# PositivePwr.net
KiCad netlist of a schematic drawn in Altium Designer
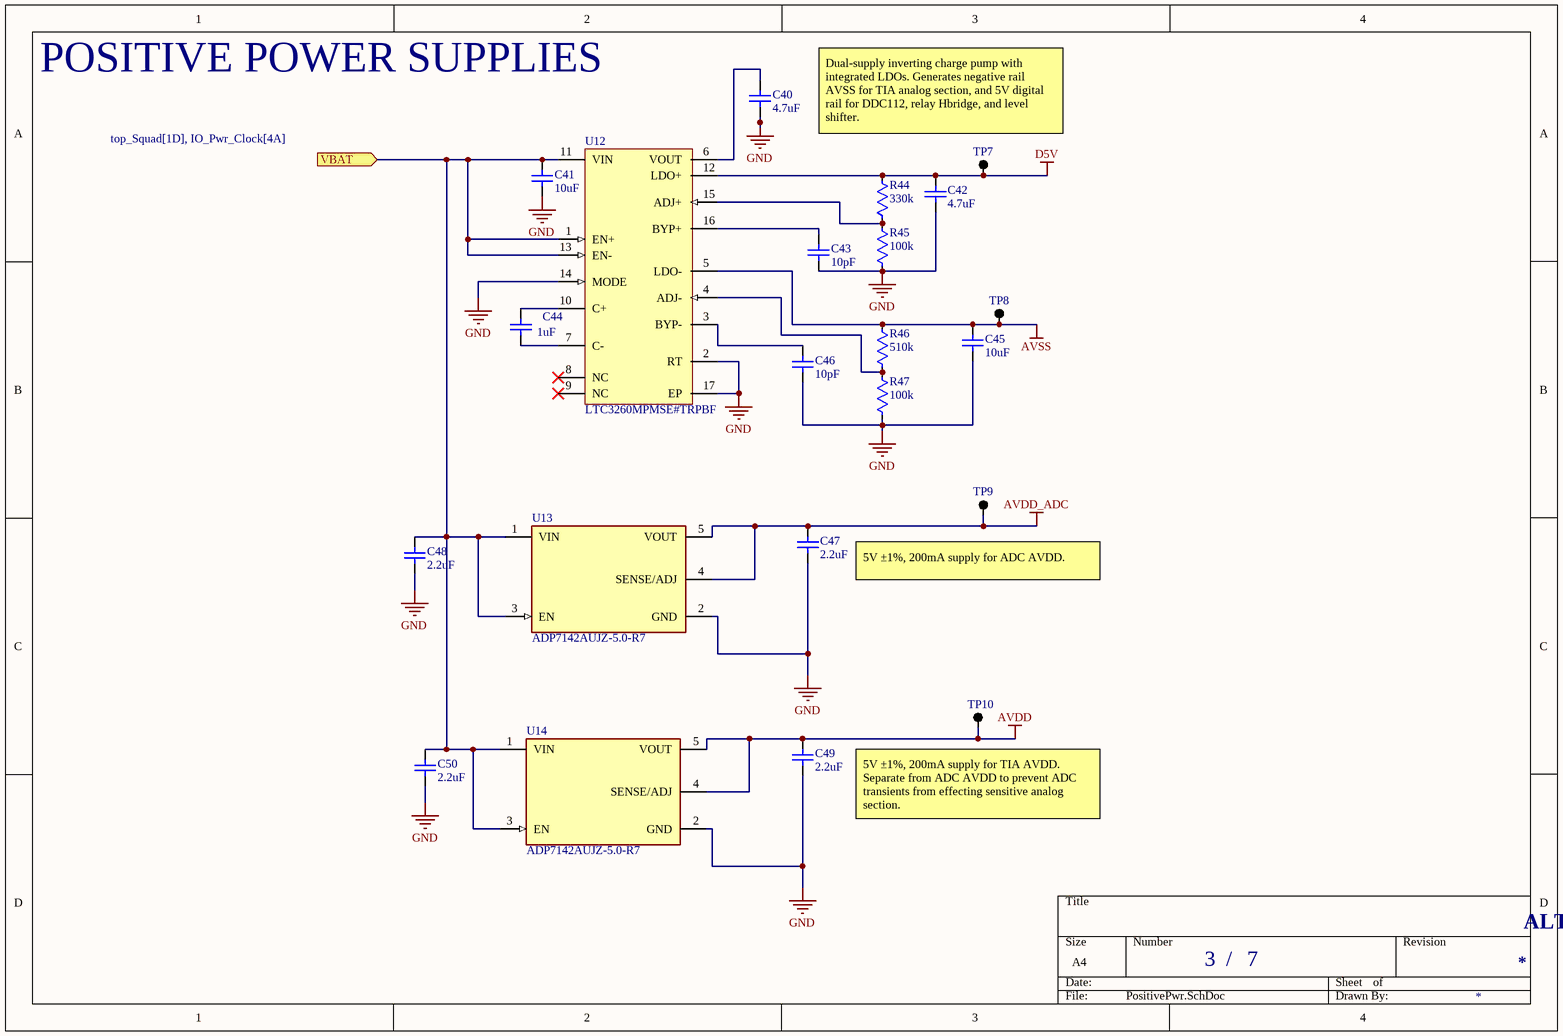
[diagram p0: PositivePwr.SchDoc]

(export (version "E")
  (design (tool "Eeschema 10.0.6"))
  (components
    (comp (ref "C40")
      (value "4.7uF")
      (footprint "CAP 0805 IPC MID DENSITY")
      (description "Murata GRM21BR61E106KA73L - Cap Ceramic 10uF 10% 25V X5R 0805")
      (fields (field (name "MF") "Murata") (field (name "MP") "GRM21BR61E106KA73L"))
      (libsource (lib "ALTAIR_PD_Capacitors") (part "CAP"))
    )
    (comp (ref "C41")
      (value "10uF")
      (footprint "CAP 0805 IPC MID DENSITY")
      (description "Murata GRM21BR61E106KA73L - Cap Ceramic 10uF 10% 25V X5R 0805")
      (fields (field (name "MF") "Murata") (field (name "MP") "GRM21BR61E106KA73L"))
      (libsource (lib "ALTAIR_PD_Capacitors") (part "CAP"))
    )
    (comp (ref "C42")
      (value "4.7uF")
      (footprint "CAP 0805 IPC MID DENSITY")
      (description "Murata GRM21BR61E106KA73L - Cap Ceramic 10uF 10% 25V X5R 0805")
      (fields (field (name "MF") "Murata") (field (name "MP") "GRM21BR61E106KA73L"))
      (libsource (lib "ALTAIR_PD_Capacitors") (part "CAP"))
    )
    (comp (ref "C43")
      (value "10pF")
      (footprint "CAP 0603 IPC MID DENSITY MURATA")
      (description "Murata GRM21BR61E106KA73L - Cap Ceramic 10uF 10% 25V X5R 0805")
      (fields (field (name "MF") "Murata") (field (name "MP") "GRM21BR61E106KA73L"))
      (libsource (lib "ALTAIR_PD_Capacitors") (part "CAP"))
    )
    (comp (ref "C44")
      (value "1uF")
      (footprint "CAP 0805 IPC MID DENSITY")
      (description "Murata GRM21BR61E106KA73L - Cap Ceramic 10uF 10% 25V X5R 0805")
      (fields (field (name "MF") "Murata") (field (name "MP") "GRM21BR61E106KA73L"))
      (libsource (lib "ALTAIR_PD_Capacitors") (part "CAP"))
    )
    (comp (ref "C45")
      (value "10uF")
      (footprint "CAP 0805 IPC MID DENSITY")
      (description "Murata GRM21BR61E106KA73L - Cap Ceramic 10uF 10% 25V X5R 0805")
      (fields (field (name "MF") "Murata") (field (name "MP") "GRM21BR61E106KA73L"))
      (libsource (lib "ALTAIR_PD_Capacitors") (part "CAP"))
    )
    (comp (ref "C46")
      (value "10pF")
      (footprint "CAP 0603 IPC MID DENSITY MURATA")
      (description "Murata GRM21BR61E106KA73L - Cap Ceramic 10uF 10% 25V X5R 0805")
      (fields (field (name "MF") "Murata") (field (name "MP") "GRM21BR61E106KA73L"))
      (libsource (lib "ALTAIR_PD_Capacitors") (part "CAP"))
    )
    (comp (ref "C47")
      (value "2.2uF")
      (footprint "CAP 1206 UNKNOWN")
      (description "CL31B225KBHNNNE CAP CER 2.2UF 50V X7R 1206")
      (fields (field (name "MF") "Samsung Electro-Mechanics") (field (name "MP") "CL31B225KBHNNNE"))
      (libsource (lib "ALTAIR_PD_Capacitors") (part "CAP"))
    )
    (comp (ref "C48")
      (value "2.2uF")
      (footprint "CAP 1206 UNKNOWN")
      (description "CL31B225KBHNNNE CAP CER 2.2UF 50V X7R 1206")
      (fields (field (name "MF") "Samsung Electro-Mechanics") (field (name "MP") "CL31B225KBHNNNE"))
      (libsource (lib "ALTAIR_PD_Capacitors") (part "CAP"))
    )
    (comp (ref "C49")
      (value "2.2uF")
      (footprint "CAP 1206 UNKNOWN")
      (description "CL31B225KBHNNNE CAP CER 2.2UF 50V X7R 1206")
      (fields (field (name "MF") "Samsung Electro-Mechanics") (field (name "MP") "CL31B225KBHNNNE"))
      (libsource (lib "ALTAIR_PD_Capacitors") (part "CAP"))
    )
    (comp (ref "C50")
      (value "2.2uF")
      (footprint "CAP 1206 UNKNOWN")
      (description "CL31B225KBHNNNE CAP CER 2.2UF 50V X7R 1206")
      (fields (field (name "MF") "Samsung Electro-Mechanics") (field (name "MP") "CL31B225KBHNNNE"))
      (libsource (lib "ALTAIR_PD_Capacitors") (part "CAP"))
    )
    (comp (ref "R44")
      (value "330k")
      (footprint "RES 0603 IPC MID DENSITY")
      (description "Panasonic ERJ-3EKF2001V Res Thick Film 0603 2K Ohm 1% 1/10W ±100ppm/°C")
      (fields (field (name "MF") "Panasonic Electronic Components") (field (name "MP") "ERJ-3EKF2001V"))
      (libsource (lib "ALTAIR_PD_Resistors") (part "RES"))
    )
    (comp (ref "R45")
      (value "100k")
      (footprint "RES 0603 IPC MID DENSITY")
      (description "Panasonic ERJ-3EKF2001V Res Thick Film 0603 2K Ohm 1% 1/10W ±100ppm/°C")
      (fields (field (name "MF") "Panasonic Electronic Components") (field (name "MP") "ERJ-3EKF2001V"))
      (libsource (lib "ALTAIR_PD_Resistors") (part "RES"))
    )
    (comp (ref "R46")
      (value "510k")
      (footprint "RES 0603 IPC MID DENSITY")
      (description "Panasonic ERJ-3EKF2001V Res Thick Film 0603 2K Ohm 1% 1/10W ±100ppm/°C")
      (fields (field (name "MF") "Panasonic Electronic Components") (field (name "MP") "ERJ-3EKF2001V"))
      (libsource (lib "ALTAIR_PD_Resistors") (part "RES"))
    )
    (comp (ref "R47")
      (value "100k")
      (footprint "RES 0603 IPC MID DENSITY")
      (description "Panasonic ERJ-3EKF2001V Res Thick Film 0603 2K Ohm 1% 1/10W ±100ppm/°C")
      (fields (field (name "MF") "Panasonic Electronic Components") (field (name "MP") "ERJ-3EKF2001V"))
      (libsource (lib "ALTAIR_PD_Resistors") (part "RES"))
    )
    (comp (ref "TP7")
      (value "Testpoint")
      (footprint "TESTPOINT THT")
      (libsource (lib "ALTAIR_PD_Testpoint") (part "Testpoint"))
    )
    (comp (ref "TP8")
      (value "Testpoint")
      (footprint "TESTPOINT THT")
      (libsource (lib "ALTAIR_PD_Testpoint") (part "Testpoint"))
    )
    (comp (ref "TP9")
      (value "Testpoint")
      (footprint "TESTPOINT THT")
      (libsource (lib "ALTAIR_PD_Testpoint") (part "Testpoint"))
    )
    (comp (ref "TP10")
      (value "Testpoint")
      (footprint "TESTPOINT THT")
      (libsource (lib "ALTAIR_PD_Testpoint") (part "Testpoint"))
    )
    (comp (ref "U12")
      (value "LTC3260MPMSE#TRPBF")
      (footprint "LT-MSE-16-EDP_L")
      (fields (field (name "MANUFACTURER") "Linear Technology"))
      (libsource (lib "ALTAIR_PD_Converters") (part "CMP-0475-00262-1"))
    )
    (comp (ref "U13")
      (value "ADP7142AUJZ-5.0-R7")
      (footprint "SOT23-5 HIGH DENSITY AD")
      (description "1.2-40V 200mA Low Noise CMOS LDO Adjustable Linear Regulator TSOT23")
      (fields
        (field (name "OCTOPART") "https://octopart.com/adp7142aujz-r7-analog+devices-38928114")
        (field (name "MF") "Analog Devices")
      )
      (libsource (lib "ALTAIR_PD_Regulators") (part "ADP7142AUJZ-R7"))
    )
    (comp (ref "U14")
      (value "ADP7142AUJZ-5.0-R7")
      (footprint "SOT23-5 HIGH DENSITY AD")
      (description "1.2-40V 200mA Low Noise CMOS LDO Adjustable Linear Regulator TSOT23")
      (fields
        (field (name "OCTOPART") "https://octopart.com/adp7142aujz-r7-analog+devices-38928114")
        (field (name "MF") "Analog Devices")
      )
      (libsource (lib "ALTAIR_PD_Regulators") (part "ADP7142AUJZ-R7"))
    )
  )
  (nets
    (net (code "1") (name "/VBAT") (class "Default")
      (node (ref "C41") (pin "2") (pinfunction "2_2") (pintype "passive"))
      (node (ref "C48") (pin "1") (pinfunction "1_1") (pintype "passive"))
      (node (ref "C50") (pin "1") (pinfunction "1_1") (pintype "passive"))
      (node (ref "U12") (pin "1") (pinfunction "EN+_1") (pintype "input"))
      (node (ref "U12") (pin "11") (pinfunction "VIN_11") (pintype "power_in"))
      (node (ref "U12") (pin "13") (pinfunction "EN-_13") (pintype "input"))
      (node (ref "U13") (pin "1") (pinfunction "VIN_1") (pintype "power_in"))
      (node (ref "U13") (pin "3") (pinfunction "EN_3") (pintype "input"))
      (node (ref "U14") (pin "1") (pinfunction "VIN_1") (pintype "power_in"))
      (node (ref "U14") (pin "3") (pinfunction "EN_3") (pintype "input"))
    )
    (net (code "2") (name "AVDD") (class "Default")
      (node (ref "C49") (pin "1") (pinfunction "1_1") (pintype "passive"))
      (node (ref "TP10") (pin "1") (pinfunction "1_1") (pintype "passive"))
      (node (ref "U14") (pin "4") (pinfunction "SENSE/ADJ_4") (pintype "passive"))
      (node (ref "U14") (pin "5") (pinfunction "VOUT_5") (pintype "passive"))
    )
    (net (code "3") (name "AVDD_ADC") (class "Default")
      (node (ref "C47") (pin "1") (pinfunction "1_1") (pintype "passive"))
      (node (ref "TP9") (pin "1") (pinfunction "1_1") (pintype "passive"))
      (node (ref "U13") (pin "4") (pinfunction "SENSE/ADJ_4") (pintype "passive"))
      (node (ref "U13") (pin "5") (pinfunction "VOUT_5") (pintype "passive"))
    )
    (net (code "4") (name "AVSS") (class "Default")
      (node (ref "C45") (pin "2") (pinfunction "2_2") (pintype "passive"))
      (node (ref "R46") (pin "2") (pinfunction "2_2") (pintype "passive"))
      (node (ref "TP8") (pin "1") (pinfunction "1_1") (pintype "passive"))
      (node (ref "U12") (pin "5") (pinfunction "LDO-_5") (pintype "power_in"))
    )
    (net (code "5") (name "D5V") (class "Default")
      (node (ref "C42") (pin "2") (pinfunction "2_2") (pintype "passive"))
      (node (ref "R44") (pin "2") (pinfunction "2_2") (pintype "passive"))
      (node (ref "TP7") (pin "1") (pinfunction "1_1") (pintype "passive"))
      (node (ref "U12") (pin "12") (pinfunction "LDO+_12") (pintype "power_in"))
    )
    (net (code "6") (name "GND") (class "Default")
      (node (ref "C40") (pin "1") (pinfunction "1_1") (pintype "passive"))
      (node (ref "C41") (pin "1") (pinfunction "1_1") (pintype "passive"))
      (node (ref "C42") (pin "1") (pinfunction "1_1") (pintype "passive"))
      (node (ref "C43") (pin "1") (pinfunction "1_1") (pintype "passive"))
      (node (ref "C45") (pin "1") (pinfunction "1_1") (pintype "passive"))
      (node (ref "C46") (pin "1") (pinfunction "1_1") (pintype "passive"))
      (node (ref "C47") (pin "2") (pinfunction "2_2") (pintype "passive"))
      (node (ref "C48") (pin "2") (pinfunction "2_2") (pintype "passive"))
      (node (ref "C49") (pin "2") (pinfunction "2_2") (pintype "passive"))
      (node (ref "C50") (pin "2") (pinfunction "2_2") (pintype "passive"))
      (node (ref "R45") (pin "1") (pinfunction "1_1") (pintype "passive"))
      (node (ref "R47") (pin "1") (pinfunction "1_1") (pintype "passive"))
      (node (ref "U12") (pin "14") (pinfunction "MODE_14") (pintype "input"))
      (node (ref "U12") (pin "17") (pinfunction "EP_17") (pintype "power_in"))
      (node (ref "U12") (pin "2") (pinfunction "RT_2") (pintype "passive"))
      (node (ref "U13") (pin "2") (pinfunction "GND_2") (pintype "power_in"))
      (node (ref "U14") (pin "2") (pinfunction "GND_2") (pintype "power_in"))
    )
    (net (code "7") (name "Net-(U12-ADJ+)") (class "Default")
      (node (ref "R44") (pin "1") (pinfunction "1_1") (pintype "passive"))
      (node (ref "R45") (pin "2") (pinfunction "2_2") (pintype "passive"))
      (node (ref "U12") (pin "15") (pinfunction "ADJ+_15") (pintype "input"))
    )
    (net (code "8") (name "Net-(U12-ADJ-)") (class "Default")
      (node (ref "R46") (pin "1") (pinfunction "1_1") (pintype "passive"))
      (node (ref "R47") (pin "2") (pinfunction "2_2") (pintype "passive"))
      (node (ref "U12") (pin "4") (pinfunction "ADJ-_4") (pintype "input"))
    )
    (net (code "9") (name "Net-(U12-BYP+)") (class "Default")
      (node (ref "C43") (pin "2") (pinfunction "2_2") (pintype "passive"))
      (node (ref "U12") (pin "16") (pinfunction "BYP+_16") (pintype "passive"))
    )
    (net (code "10") (name "Net-(U12-BYP-)") (class "Default")
      (node (ref "C46") (pin "2") (pinfunction "2_2") (pintype "passive"))
      (node (ref "U12") (pin "3") (pinfunction "BYP-_3") (pintype "passive"))
    )
    (net (code "11") (name "Net-(U12-C+)") (class "Default")
      (node (ref "C44") (pin "2") (pinfunction "2_2") (pintype "passive"))
      (node (ref "U12") (pin "10") (pinfunction "C+_10") (pintype "passive"))
    )
    (net (code "12") (name "Net-(U12-C-)") (class "Default")
      (node (ref "C44") (pin "1") (pinfunction "1_1") (pintype "passive"))
      (node (ref "U12") (pin "7") (pinfunction "C-_7") (pintype "passive"))
    )
    (net (code "13") (name "Net-(U12-VOUT)") (class "Default")
      (node (ref "C40") (pin "2") (pinfunction "2_2") (pintype "passive"))
      (node (ref "U12") (pin "6") (pinfunction "VOUT_6") (pintype "power_in"))
    )
    (net (code "14") (name "unconnected-(U12-NC-Pad8)") (class "Default")
      (node (ref "U12") (pin "8") (pinfunction "NC_8") (pintype "passive+no_connect"))
    )
    (net (code "15") (name "unconnected-(U12-NC-Pad9)") (class "Default")
      (node (ref "U12") (pin "9") (pinfunction "NC_9") (pintype "passive+no_connect"))
    )
  )
)
